# Sheet1.net
KiCad netlist of a schematic drawn in Altium Designer
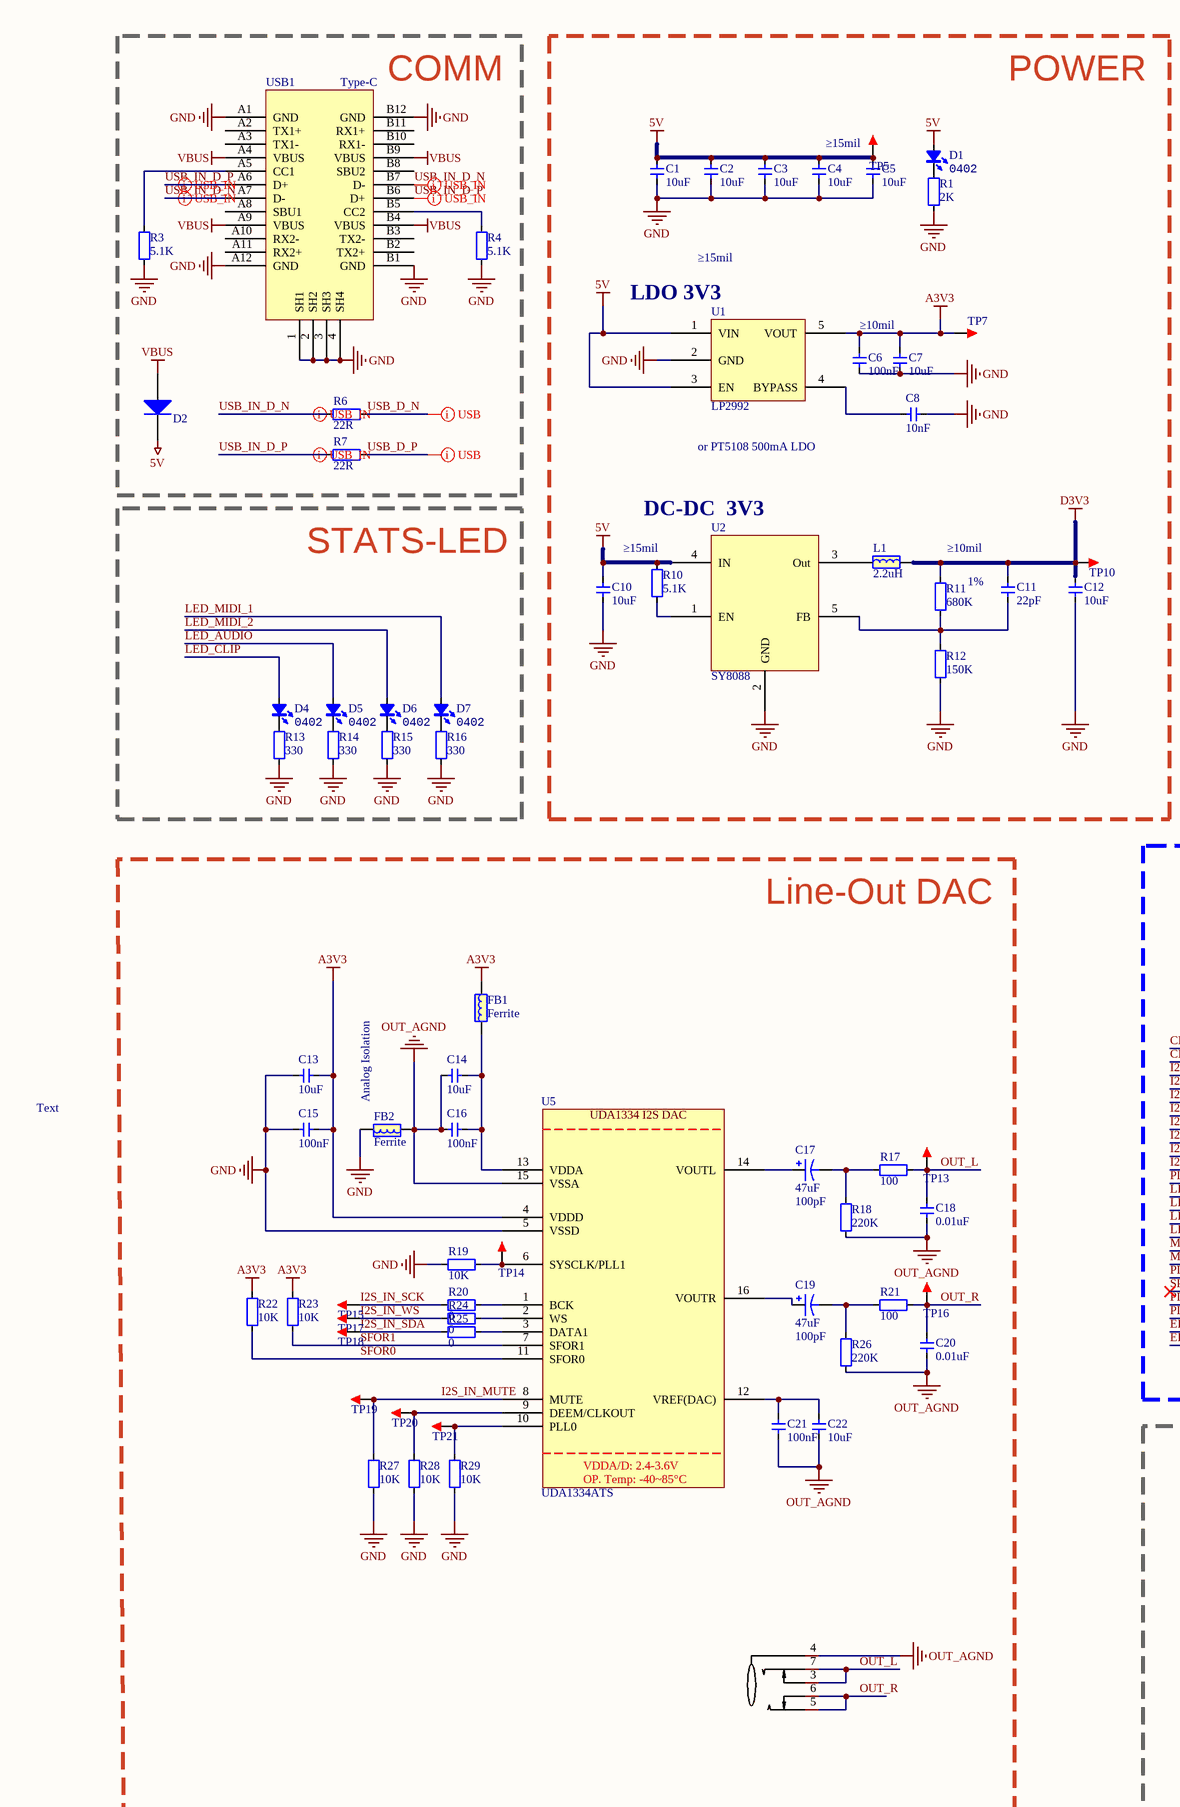
[diagram p0: Sheet1.SchDoc, left]
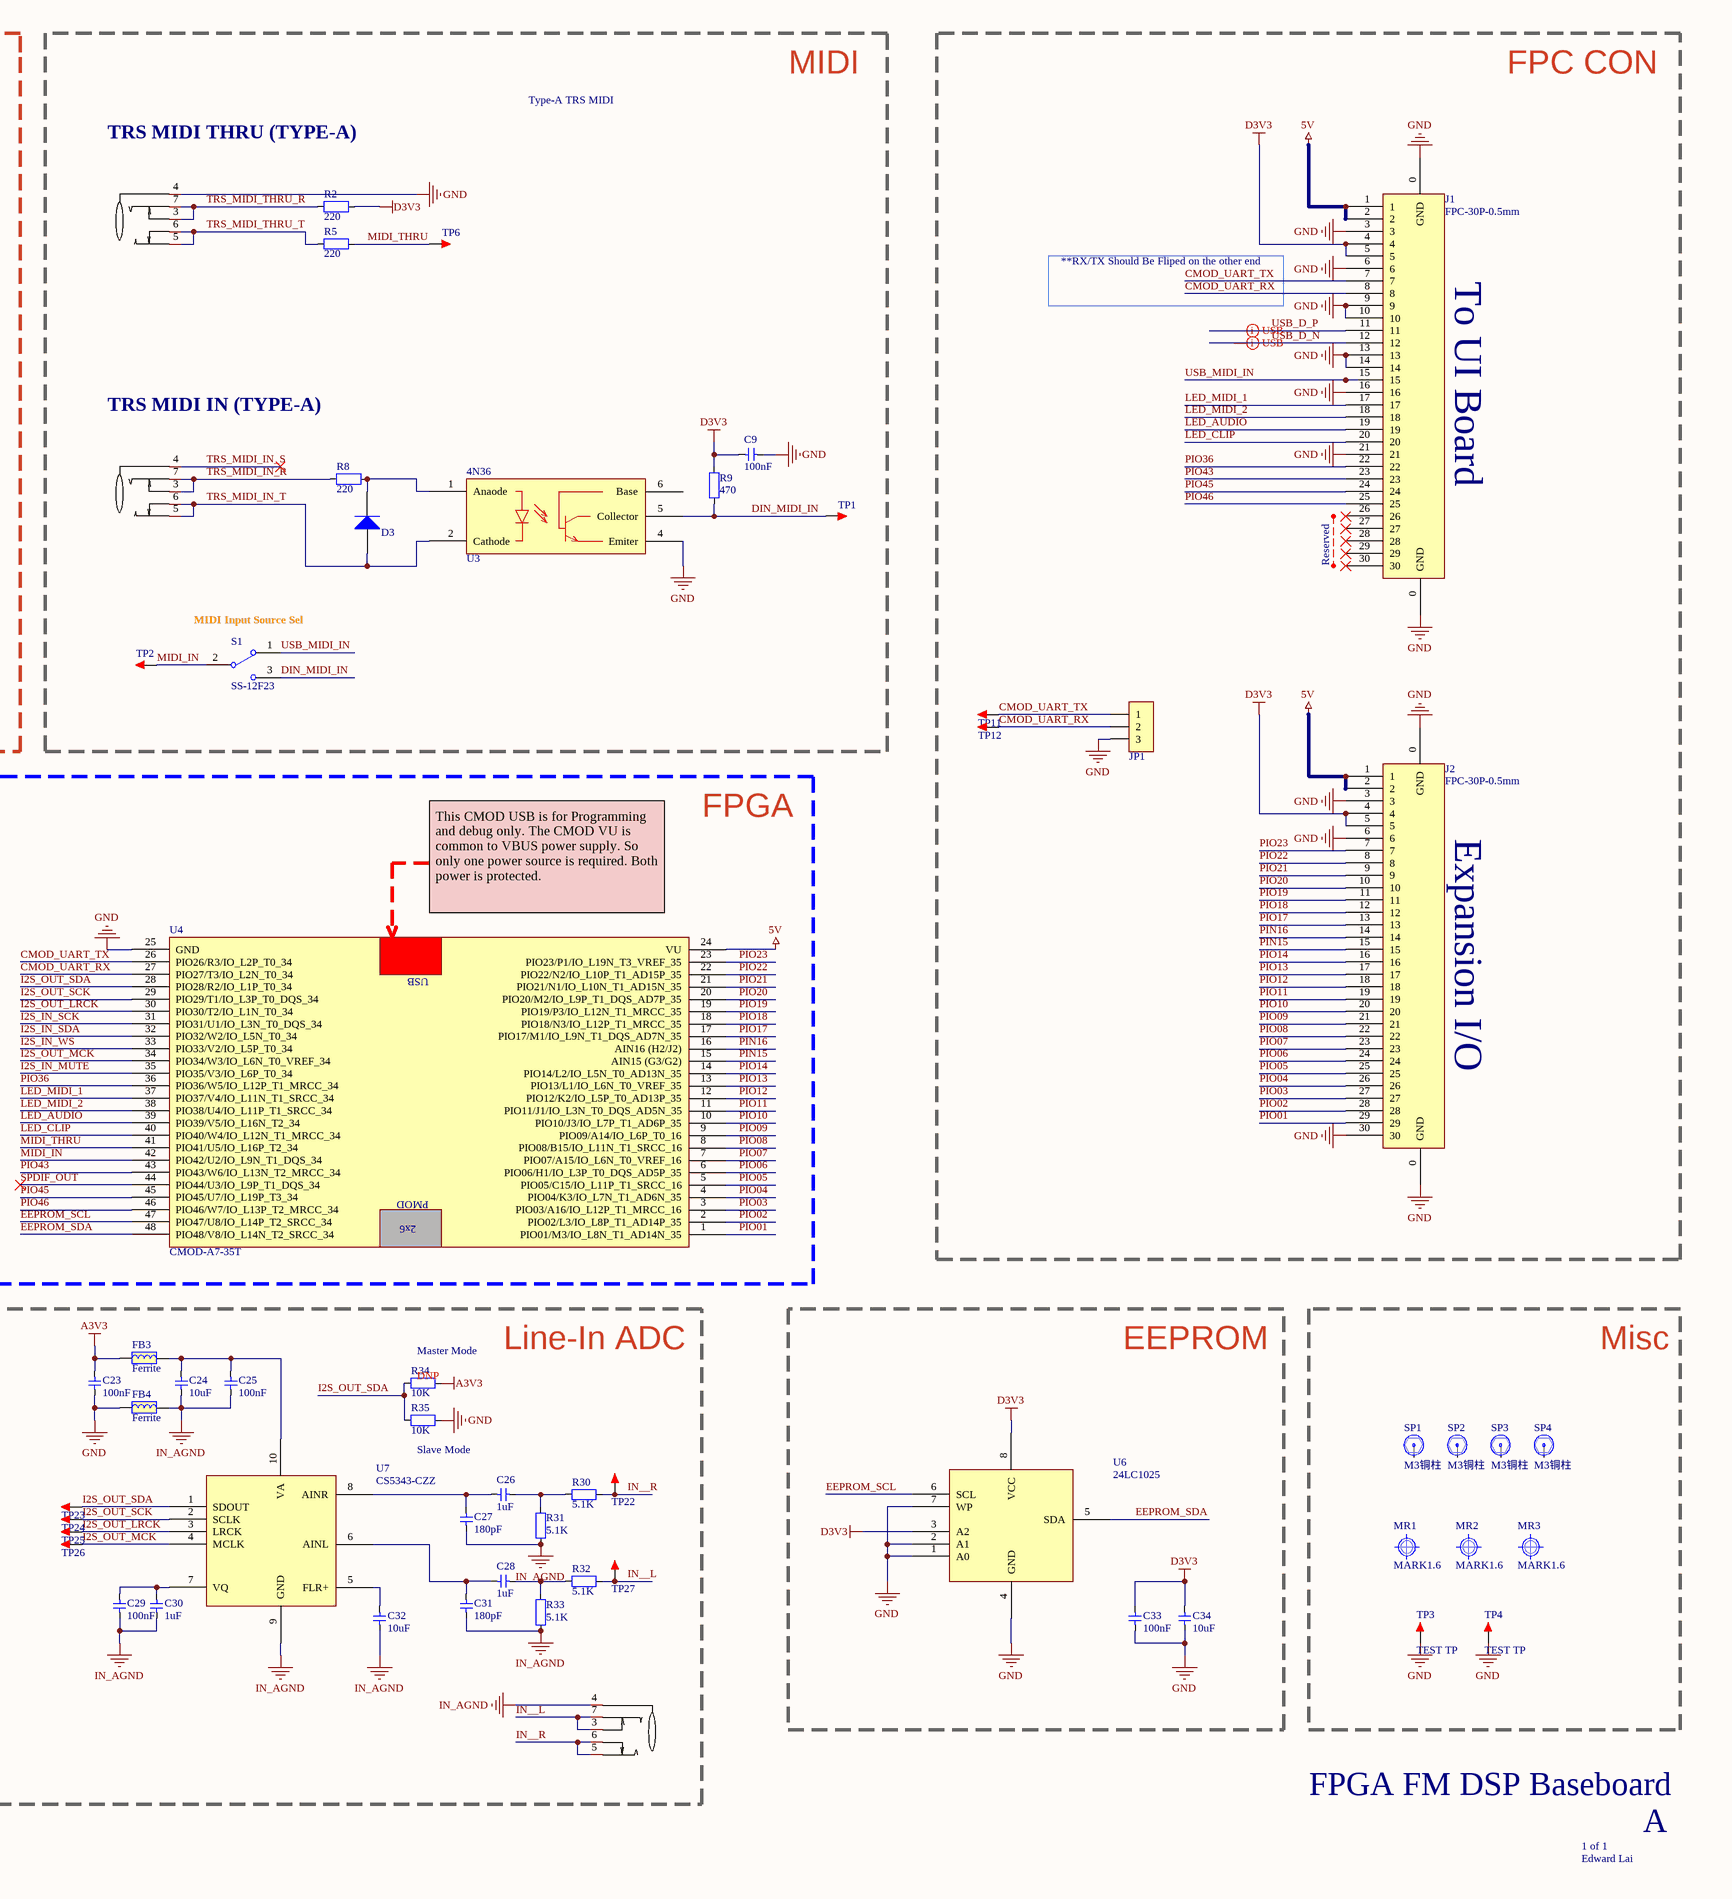
[diagram p1: Sheet1.SchDoc, right]

(export (version "E")
  (design (tool "Eeschema 10.0.6"))
  (components
    (comp (ref "C1")
      (value "10uF")
      (footprint "C0402_L")
      (description "Capacitor")
      (libsource (lib "MyPcbLib") (part "电容-1206"))
    )
    (comp (ref "C2")
      (value "10uF")
      (footprint "C0402_L")
      (description "Capacitor")
      (libsource (lib "MyPcbLib") (part "电容-1206"))
    )
    (comp (ref "C3")
      (value "10uF")
      (footprint "C0402_L")
      (description "Capacitor")
      (libsource (lib "MyPcbLib") (part "电容-1206"))
    )
    (comp (ref "C4")
      (value "10uF")
      (footprint "C0402_L")
      (description "Capacitor")
      (libsource (lib "MyPcbLib") (part "电容-1206"))
    )
    (comp (ref "C5")
      (value "10uF")
      (footprint "C0402_L")
      (description "Capacitor")
      (libsource (lib "MyPcbLib") (part "电容-1206"))
    )
    (comp (ref "C6")
      (value "100nF")
      (footprint "C0402_L")
      (description "Capacitor")
      (libsource (lib "MyPcbLib") (part "电容-0402"))
    )
    (comp (ref "C7")
      (value "10uF")
      (footprint "C0402_L")
      (description "Capacitor")
      (libsource (lib "MyPcbLib") (part "电容-0402"))
    )
    (comp (ref "C8")
      (value "10nF")
      (footprint "C0402_L")
      (description "Capacitor")
      (libsource (lib "MyPcbLib") (part "电容-0402"))
    )
    (comp (ref "C9")
      (value "100nF")
      (footprint "C0402_L")
      (description "Capacitor")
      (libsource (lib "MyPcbLib") (part "电容-0402"))
    )
    (comp (ref "C10")
      (value "10uF")
      (footprint "C0402_L")
      (description "Capacitor")
      (libsource (lib "MyPcbLib") (part "电容-0402"))
    )
    (comp (ref "C11")
      (value "22pF")
      (footprint "C0402_L")
      (description "Capacitor")
      (libsource (lib "MyPcbLib") (part "电容-0402"))
    )
    (comp (ref "C12")
      (value "10uF")
      (footprint "C0402_L")
      (description "Capacitor")
      (libsource (lib "MyPcbLib") (part "电容-0402"))
    )
    (comp (ref "C13")
      (value "10uF")
      (footprint "C0402_L")
      (description "Capacitor")
      (libsource (lib "MyPcbLib") (part "电容-0402"))
    )
    (comp (ref "C14")
      (value "10uF")
      (footprint "C0402_L")
      (description "Capacitor")
      (libsource (lib "MyPcbLib") (part "电容-0402"))
    )
    (comp (ref "C15")
      (value "100nF")
      (footprint "C0402_L")
      (description "Capacitor")
      (libsource (lib "MyPcbLib") (part "电容-0402"))
    )
    (comp (ref "C16")
      (value "100nF")
      (footprint "C0402_L")
      (description "Capacitor")
      (libsource (lib "MyPcbLib") (part "电容-0402"))
    )
    (comp (ref "C17")
      (value "47uF")
      (footprint "CT 5*6 - B")
      (description "Polarized Capacitor SMT")
      (fields (field (name "ALTIUM_VALUE") "100pF") (field (name "PUBLISHER") "Altium Limited"))
      (libsource (lib "Miscellaneous Devices") (part "Cap Pol1"))
    )
    (comp (ref "C18")
      (value "0.01uF")
      (footprint "C0603_L")
      (description "Capacitor")
      (libsource (lib "MyPcbLib") (part "电容-0402"))
    )
    (comp (ref "C19")
      (value "47uF")
      (footprint "CT 5*6 - B")
      (description "Polarized Capacitor SMT")
      (fields (field (name "ALTIUM_VALUE") "100pF") (field (name "PUBLISHER") "Altium Limited"))
      (libsource (lib "Miscellaneous Devices") (part "Cap Pol1"))
    )
    (comp (ref "C20")
      (value "0.01uF")
      (footprint "C0603_L")
      (description "Capacitor")
      (libsource (lib "MyPcbLib") (part "电容-0402"))
    )
    (comp (ref "C21")
      (value "100nF")
      (footprint "C0402_L")
      (description "Capacitor")
      (libsource (lib "MyPcbLib") (part "电容-0402"))
    )
    (comp (ref "C22")
      (value "10uF")
      (footprint "C0402_L")
      (description "Capacitor")
      (libsource (lib "MyPcbLib") (part "电容-0402"))
    )
    (comp (ref "C23")
      (value "100nF")
      (footprint "C0402_L")
      (description "Capacitor")
      (libsource (lib "MyPcbLib") (part "电容-0402"))
    )
    (comp (ref "C24")
      (value "10uF")
      (footprint "C0402_L")
      (description "Capacitor")
      (libsource (lib "MyPcbLib") (part "电容-0402"))
    )
    (comp (ref "C25")
      (value "100nF")
      (footprint "C0402_L")
      (description "Capacitor")
      (libsource (lib "MyPcbLib") (part "电容-0402"))
    )
    (comp (ref "C26")
      (value "1uF")
      (footprint "C0402_L")
      (description "Capacitor")
      (libsource (lib "MyPcbLib") (part "电容-0402"))
    )
    (comp (ref "C27")
      (value "180pF")
      (footprint "C0402_L")
      (description "Capacitor")
      (libsource (lib "MyPcbLib") (part "电容-0402"))
    )
    (comp (ref "C28")
      (value "1uF")
      (footprint "C0402_L")
      (description "Capacitor")
      (libsource (lib "MyPcbLib") (part "电容-0402"))
    )
    (comp (ref "C29")
      (value "100nF")
      (footprint "C0402_L")
      (description "Capacitor")
      (libsource (lib "MyPcbLib") (part "电容-0402"))
    )
    (comp (ref "C30")
      (value "1uF")
      (footprint "C0402_L")
      (description "Capacitor")
      (libsource (lib "MyPcbLib") (part "电容-0402"))
    )
    (comp (ref "C31")
      (value "180pF")
      (footprint "C0402_L")
      (description "Capacitor")
      (libsource (lib "MyPcbLib") (part "电容-0402"))
    )
    (comp (ref "C32")
      (value "10uF")
      (footprint "C0402_L")
      (description "Capacitor")
      (libsource (lib "MyPcbLib") (part "电容-0402"))
    )
    (comp (ref "C33")
      (value "100nF")
      (footprint "C0402_L")
      (description "Capacitor")
      (libsource (lib "MyPcbLib") (part "电容-0402"))
    )
    (comp (ref "C34")
      (value "10uF")
      (footprint "C0402_L")
      (description "Capacitor")
      (libsource (lib "MyPcbLib") (part "电容-0402"))
    )
    (comp (ref "CN1")
      (value "PJ-328-5A")
      (footprint "AUDIO-SMD_PJ-328-5A")
      (fields (field (name "MANUFACTURER") "韩国韩荣"))
      (libsource (lib "altium-import") (part "root_0_PJ-328-5A_"))
    )
    (comp (ref "CN2")
      (value "PJ-328-5A")
      (footprint "AUDIO-SMD_PJ-328-5A")
      (fields (field (name "MANUFACTURER") "韩国韩荣"))
      (libsource (lib "altium-import") (part "root_0_PJ-328-5A_"))
    )
    (comp (ref "CN3")
      (value "PJ-328-5A")
      (footprint "AUDIO-SMD_PJ-328-5A")
      (fields (field (name "MANUFACTURER") "韩国韩荣"))
      (libsource (lib "altium-import") (part "root_0_PJ-328-5A_"))
    )
    (comp (ref "CN4")
      (value "PJ-328-5A")
      (footprint "AUDIO-SMD_PJ-328-5A")
      (fields (field (name "MANUFACTURER") "韩国韩荣"))
      (libsource (lib "altium-import") (part "root_0_mirrored_PJ-328-5A_"))
    )
    (comp (ref "D1")
      (value "color?")
      (footprint "LED0603_R")
      (description "LED")
      (fields (field (name "TYPE") "0402"))
      (libsource (lib "KitSprout") (part "LED_0402"))
    )
    (comp (ref "D2")
      (value "二极管-5B5819WS")
      (footprint "SOD-323")
      (description "40V")
      (libsource (lib "MyPcbLib") (part "二极管-5B5817WS"))
    )
    (comp (ref "D3")
      (value "Diode")
      (footprint "SOD-523")
      (description "1N1418")
      (libsource (lib "0.2 - 二极管-TVS-ESD-整流桥") (part "Diode"))
    )
    (comp (ref "D4")
      (value "color?")
      (footprint "LED0603_R")
      (description "LED")
      (fields (field (name "TYPE") "0402"))
      (libsource (lib "KitSprout") (part "LED_0402"))
    )
    (comp (ref "D5")
      (value "color?")
      (footprint "LED0603_G")
      (description "LED")
      (fields (field (name "TYPE") "0402"))
      (libsource (lib "KitSprout") (part "LED_0402"))
    )
    (comp (ref "D6")
      (value "color?")
      (footprint "LED0603_W")
      (description "LED")
      (fields (field (name "TYPE") "0402"))
      (libsource (lib "KitSprout") (part "LED_0402"))
    )
    (comp (ref "D7")
      (value "color?")
      (footprint "LED0603_W")
      (description "LED")
      (fields (field (name "TYPE") "0402"))
      (libsource (lib "KitSprout") (part "LED_0402"))
    )
    (comp (ref "FB1") (value "Ferrite") (footprint "L0402") (libsource (lib "") (part "电感-201612_2")))
    (comp (ref "FB2") (value "Ferrite") (footprint "L0402") (libsource (lib "MyPcbLib") (part "电感-201612")))
    (comp (ref "FB3") (value "Ferrite") (footprint "L0402") (libsource (lib "") (part "电感-201612_1")))
    (comp (ref "FB4") (value "Ferrite") (footprint "L0402") (libsource (lib "") (part "电感-201612_1")))
    (comp (ref "J1")
      (value "FPC-30P-0.5mm")
      (footprint "FPC0.5-WT-30P")
      (libsource (lib "Schlib2") (part "FPC-30P-0.5mm"))
    )
    (comp (ref "J2")
      (value "FPC-30P-0.5mm")
      (footprint "FPC0.5-WT-30P")
      (libsource (lib "Schlib2") (part "FPC-30P-0.5mm"))
    )
    (comp (ref "JP1")
      (value "HDR-1X3")
      (footprint "XH2.54-LS-3P")
      (description "3P接插件")
      (libsource (lib "5.5 - 2.54mm(100mil)连接器(XH2.54)") (part "Header 3"))
    )
    (comp (ref "L1") (value "2.2uH") (footprint "IND-201612") (libsource (lib "") (part "电感-201612_1")))
    (comp (ref "MR1")
      (value "MARK1.6")
      (footprint "Mark 1.6")
      (description "光学定位点")
      (libsource (lib "0.5 - 按键-开关-蜂鸣器-保险丝-电池-测试点-Mark点") (part "MARK"))
    )
    (comp (ref "MR2")
      (value "MARK1.6")
      (footprint "Mark 1.6")
      (description "光学定位点")
      (libsource (lib "0.5 - 按键-开关-蜂鸣器-保险丝-电池-测试点-Mark点") (part "MARK"))
    )
    (comp (ref "MR3")
      (value "MARK1.6")
      (footprint "Mark 1.6")
      (description "光学定位点")
      (libsource (lib "0.5 - 按键-开关-蜂鸣器-保险丝-电池-测试点-Mark点") (part "MARK"))
    )
    (comp (ref "R1")
      (value "2K")
      (footprint "R0402_L")
      (description "Resistor")
      (libsource (lib "") (part "电阻-0402_2"))
    )
    (comp (ref "R2")
      (value "220")
      (footprint "R0402_L")
      (description "Resistor")
      (libsource (lib "") (part "电阻-0402_3"))
    )
    (comp (ref "R3")
      (value "5.1K")
      (footprint "R0402_L")
      (description "Resistor")
      (libsource (lib "MyPcbLib") (part "电阻-0402"))
    )
    (comp (ref "R4")
      (value "5.1K")
      (footprint "R0402_L")
      (description "Resistor")
      (libsource (lib "MyPcbLib") (part "电阻-0402"))
    )
    (comp (ref "R5")
      (value "220")
      (footprint "R0402_L")
      (description "Resistor")
      (libsource (lib "") (part "电阻-0402_3"))
    )
    (comp (ref "R6")
      (value "22R")
      (footprint "R0402_L")
      (description "Resistor")
      (libsource (lib "") (part "电阻-0402_1"))
    )
    (comp (ref "R7")
      (value "22R")
      (footprint "R0402_L")
      (description "Resistor")
      (libsource (lib "") (part "电阻-0402_1"))
    )
    (comp (ref "R8")
      (value "220")
      (footprint "R0402_L")
      (description "Resistor")
      (libsource (lib "") (part "电阻-0402_3"))
    )
    (comp (ref "R9")
      (value "470")
      (footprint "R0402_L")
      (description "Resistor")
      (libsource (lib "") (part "电阻-0402_2"))
    )
    (comp (ref "R10")
      (value "5.1K")
      (footprint "R0402_L")
      (description "Resistor")
      (libsource (lib "MyPcbLib") (part "电阻-0402"))
    )
    (comp (ref "R11")
      (value "680K")
      (footprint "R0402_L")
      (description "Resistor")
      (fields (field (name "PARAMETER 1") "1%"))
      (libsource (lib "MyPcbLib") (part "电阻-0402"))
    )
    (comp (ref "R12")
      (value "150K")
      (footprint "R0402_L")
      (description "Resistor")
      (libsource (lib "MyPcbLib") (part "电阻-0402"))
    )
    (comp (ref "R13")
      (value "330")
      (footprint "R0402_L")
      (description "Resistor")
      (libsource (lib "") (part "电阻-0402_2"))
    )
    (comp (ref "R14")
      (value "330")
      (footprint "R0402_L")
      (description "Resistor")
      (libsource (lib "") (part "电阻-0402_2"))
    )
    (comp (ref "R15")
      (value "330")
      (footprint "R0402_L")
      (description "Resistor")
      (libsource (lib "") (part "电阻-0402_2"))
    )
    (comp (ref "R16")
      (value "330")
      (footprint "R0402_L")
      (description "Resistor")
      (libsource (lib "") (part "电阻-0402_2"))
    )
    (comp (ref "R17")
      (value "100")
      (footprint "R0603_L")
      (description "Resistor")
      (libsource (lib "") (part "电阻-0402_1"))
    )
    (comp (ref "R18")
      (value "220K")
      (footprint "R0603_L")
      (description "Resistor")
      (libsource (lib "MyPcbLib") (part "电阻-0402"))
    )
    (comp (ref "R19")
      (value "10K")
      (footprint "R0402_L")
      (description "Resistor")
      (libsource (lib "") (part "电阻-0402_1"))
    )
    (comp (ref "R20")
      (value "0")
      (footprint "R0402_L")
      (description "Resistor")
      (libsource (lib "") (part "电阻-0402_3"))
    )
    (comp (ref "R21")
      (value "100")
      (footprint "R0603_L")
      (description "Resistor")
      (libsource (lib "") (part "电阻-0402_1"))
    )
    (comp (ref "R22")
      (value "10K")
      (footprint "R0402_L")
      (description "Resistor")
      (libsource (lib "MyPcbLib") (part "电阻-0402"))
    )
    (comp (ref "R23")
      (value "10K")
      (footprint "R0402_L")
      (description "Resistor")
      (libsource (lib "MyPcbLib") (part "电阻-0402"))
    )
    (comp (ref "R24")
      (value "0")
      (footprint "R0402_L")
      (description "Resistor")
      (libsource (lib "") (part "电阻-0402_3"))
    )
    (comp (ref "R25")
      (value "0")
      (footprint "R0402_L")
      (description "Resistor")
      (libsource (lib "") (part "电阻-0402_3"))
    )
    (comp (ref "R26")
      (value "220K")
      (footprint "R0603_L")
      (description "Resistor")
      (libsource (lib "MyPcbLib") (part "电阻-0402"))
    )
    (comp (ref "R27")
      (value "10K")
      (footprint "R0402_L")
      (description "Resistor")
      (libsource (lib "MyPcbLib") (part "电阻-0402"))
    )
    (comp (ref "R28")
      (value "10K")
      (footprint "R0402_L")
      (description "Resistor")
      (libsource (lib "MyPcbLib") (part "电阻-0402"))
    )
    (comp (ref "R29")
      (value "10K")
      (footprint "R0402_L")
      (description "Resistor")
      (libsource (lib "MyPcbLib") (part "电阻-0402"))
    )
    (comp (ref "R30")
      (value "5.1K")
      (footprint "R0402_L")
      (description "Resistor")
      (libsource (lib "") (part "电阻-0402_1"))
    )
    (comp (ref "R31")
      (value "5.1K")
      (footprint "R0402_L")
      (description "Resistor")
      (libsource (lib "MyPcbLib") (part "电阻-0402"))
    )
    (comp (ref "R32")
      (value "5.1K")
      (footprint "R0402_L")
      (description "Resistor")
      (libsource (lib "") (part "电阻-0402_3"))
    )
    (comp (ref "R33")
      (value "5.1K")
      (footprint "R0402_L")
      (description "Resistor")
      (libsource (lib "MyPcbLib") (part "电阻-0402"))
    )
    (comp (ref "R34")
      (value "10K")
      (footprint "R0402_L")
      (description "Resistor")
      (libsource (lib "") (part "电阻-0402_1"))
    )
    (comp (ref "R35")
      (value "10K")
      (footprint "R0402_L")
      (description "Resistor")
      (libsource (lib "") (part "电阻-0402_1"))
    )
    (comp (ref "S1")
      (value "SS-12F23")
      (footprint "MSK-12C01-07")
      (description "1路波动开关")
      (libsource (lib "0.5 - 按键-开关-蜂鸣器-保险丝-电池-测试点-Mark点") (part "SSW-1P"))
    )
    (comp (ref "SP1")
      (value "M3铜柱")
      (footprint "M3x8_N")
      (description "铜柱")
      (libsource (lib "0.5 - 按键-开关-蜂鸣器-保险丝-电池-测试点-Mark点") (part "铜柱大焊盘"))
    )
    (comp (ref "SP2")
      (value "M3铜柱")
      (footprint "M3x8_N")
      (description "铜柱")
      (libsource (lib "0.5 - 按键-开关-蜂鸣器-保险丝-电池-测试点-Mark点") (part "铜柱大焊盘"))
    )
    (comp (ref "SP3")
      (value "M3铜柱")
      (footprint "M3x8_N")
      (description "铜柱")
      (libsource (lib "0.5 - 按键-开关-蜂鸣器-保险丝-电池-测试点-Mark点") (part "铜柱大焊盘"))
    )
    (comp (ref "SP4")
      (value "M3铜柱")
      (footprint "M3x8_N")
      (description "铜柱")
      (libsource (lib "0.5 - 按键-开关-蜂鸣器-保险丝-电池-测试点-Mark点") (part "铜柱大焊盘"))
    )
    (comp (ref "TP1")
      (value "DIN_MIDI_IN")
      (footprint "TEST 1.2")
      (description "测试环")
      (libsource (lib "0.5 - 按键-开关-蜂鸣器-保险丝-电池-测试点-Mark点") (part "TEST TP"))
    )
    (comp (ref "TP2")
      (value "MIDI_IN")
      (footprint "TEST 1.2")
      (description "测试环")
      (libsource (lib "0.5 - 按键-开关-蜂鸣器-保险丝-电池-测试点-Mark点") (part "TEST TP"))
    )
    (comp (ref "TP3")
      (value "TEST TP")
      (footprint "TEST 1.2")
      (description "测试环")
      (libsource (lib "0.5 - 按键-开关-蜂鸣器-保险丝-电池-测试点-Mark点") (part "TEST TP"))
    )
    (comp (ref "TP4")
      (value "TEST TP")
      (footprint "TEST 1.2")
      (description "测试环")
      (libsource (lib "0.5 - 按键-开关-蜂鸣器-保险丝-电池-测试点-Mark点") (part "TEST TP"))
    )
    (comp (ref "TP5")
      (value "DIN_MIDI_IN")
      (footprint "TEST 1.2")
      (description "测试环")
      (libsource (lib "0.5 - 按键-开关-蜂鸣器-保险丝-电池-测试点-Mark点") (part "TEST TP"))
    )
    (comp (ref "TP6")
      (value "DIN_MIDI_IN")
      (footprint "TEST 1.2")
      (description "测试环")
      (libsource (lib "0.5 - 按键-开关-蜂鸣器-保险丝-电池-测试点-Mark点") (part "TEST TP"))
    )
    (comp (ref "TP7")
      (value "DIN_MIDI_IN")
      (footprint "TEST 1.2")
      (description "测试环")
      (libsource (lib "0.5 - 按键-开关-蜂鸣器-保险丝-电池-测试点-Mark点") (part "TEST TP"))
    )
    (comp (ref "TP10")
      (value "DIN_MIDI_IN")
      (footprint "TEST 1.2")
      (description "测试环")
      (libsource (lib "0.5 - 按键-开关-蜂鸣器-保险丝-电池-测试点-Mark点") (part "TEST TP"))
    )
    (comp (ref "TP11")
      (value "DIN_MIDI_IN")
      (footprint "TEST 1.2")
      (description "测试环")
      (libsource (lib "0.5 - 按键-开关-蜂鸣器-保险丝-电池-测试点-Mark点") (part "TEST TP"))
    )
    (comp (ref "TP12")
      (value "DIN_MIDI_IN")
      (footprint "TEST 1.2")
      (description "测试环")
      (libsource (lib "0.5 - 按键-开关-蜂鸣器-保险丝-电池-测试点-Mark点") (part "TEST TP"))
    )
    (comp (ref "TP13")
      (value "DIN_MIDI_IN")
      (footprint "TEST 1.2")
      (description "测试环")
      (libsource (lib "0.5 - 按键-开关-蜂鸣器-保险丝-电池-测试点-Mark点") (part "TEST TP"))
    )
    (comp (ref "TP14")
      (value "DIN_MIDI_IN")
      (footprint "TEST 1.2")
      (description "测试环")
      (libsource (lib "0.5 - 按键-开关-蜂鸣器-保险丝-电池-测试点-Mark点") (part "TEST TP"))
    )
    (comp (ref "TP15")
      (value "DIN_MIDI_IN")
      (footprint "TEST 1.2")
      (description "测试环")
      (libsource (lib "0.5 - 按键-开关-蜂鸣器-保险丝-电池-测试点-Mark点") (part "TEST TP"))
    )
    (comp (ref "TP16")
      (value "DIN_MIDI_IN")
      (footprint "TEST 1.2")
      (description "测试环")
      (libsource (lib "0.5 - 按键-开关-蜂鸣器-保险丝-电池-测试点-Mark点") (part "TEST TP"))
    )
    (comp (ref "TP17")
      (value "DIN_MIDI_IN")
      (footprint "TEST 1.2")
      (description "测试环")
      (libsource (lib "0.5 - 按键-开关-蜂鸣器-保险丝-电池-测试点-Mark点") (part "TEST TP"))
    )
    (comp (ref "TP18")
      (value "DIN_MIDI_IN")
      (footprint "TEST 1.2")
      (description "测试环")
      (libsource (lib "0.5 - 按键-开关-蜂鸣器-保险丝-电池-测试点-Mark点") (part "TEST TP"))
    )
    (comp (ref "TP19")
      (value "DIN_MIDI_IN")
      (footprint "TEST 1.2")
      (description "测试环")
      (libsource (lib "0.5 - 按键-开关-蜂鸣器-保险丝-电池-测试点-Mark点") (part "TEST TP"))
    )
    (comp (ref "TP20")
      (value "DIN_MIDI_IN")
      (footprint "TEST 1.2")
      (description "测试环")
      (libsource (lib "0.5 - 按键-开关-蜂鸣器-保险丝-电池-测试点-Mark点") (part "TEST TP"))
    )
    (comp (ref "TP21")
      (value "DIN_MIDI_IN")
      (footprint "TEST 1.2")
      (description "测试环")
      (libsource (lib "0.5 - 按键-开关-蜂鸣器-保险丝-电池-测试点-Mark点") (part "TEST TP"))
    )
    (comp (ref "TP22")
      (value "DIN_MIDI_IN")
      (footprint "TEST 1.2")
      (description "测试环")
      (libsource (lib "0.5 - 按键-开关-蜂鸣器-保险丝-电池-测试点-Mark点") (part "TEST TP"))
    )
    (comp (ref "TP23")
      (value "DIN_MIDI_IN")
      (footprint "TEST 1.2")
      (description "测试环")
      (libsource (lib "0.5 - 按键-开关-蜂鸣器-保险丝-电池-测试点-Mark点") (part "TEST TP"))
    )
    (comp (ref "TP24")
      (value "DIN_MIDI_IN")
      (footprint "TEST 1.2")
      (description "测试环")
      (libsource (lib "0.5 - 按键-开关-蜂鸣器-保险丝-电池-测试点-Mark点") (part "TEST TP"))
    )
    (comp (ref "TP25")
      (value "DIN_MIDI_IN")
      (footprint "TEST 1.2")
      (description "测试环")
      (libsource (lib "0.5 - 按键-开关-蜂鸣器-保险丝-电池-测试点-Mark点") (part "TEST TP"))
    )
    (comp (ref "TP26")
      (value "DIN_MIDI_IN")
      (footprint "TEST 1.2")
      (description "测试环")
      (libsource (lib "0.5 - 按键-开关-蜂鸣器-保险丝-电池-测试点-Mark点") (part "TEST TP"))
    )
    (comp (ref "TP27")
      (value "DIN_MIDI_IN")
      (footprint "TEST 1.2")
      (description "测试环")
      (libsource (lib "0.5 - 按键-开关-蜂鸣器-保险丝-电池-测试点-Mark点") (part "TEST TP"))
    )
    (comp (ref "U1") (value "LP2992") (footprint "SOT23-5M") (libsource (lib "Schlib2") (part "LP2992")))
    (comp (ref "U2")
      (value "SY8088")
      (footprint "SOT23-5")
      (description "SY8088 High Efficiency 1.5MHz, 1A  \r\nSynchronous Step Down Regulator")
      (libsource (lib "Schlib2") (part "SY8088"))
    )
    (comp (ref "U3")
      (value "4N36")
      (footprint "OPTOCOUPLER_H11F3SR2M")
      (description "4N36\r\n6-Pin General Purpose Phototransistor Optocouplers")
      (libsource (lib "Schlib2") (part "4N36"))
    )
    (comp (ref "U4")
      (value "CMOD-A7-35T")
      (footprint "DIP48")
      (description "Digilent CMOD A7 35T")
      (libsource (lib "Schlib2") (part "CMOD-A7-35T"))
    )
    (comp (ref "U5")
      (value "UDA1334ATS")
      (footprint "SSOP16")
      (libsource (lib "Schlib2") (part "UDA1334ATS"))
    )
    (comp (ref "U6")
      (value "24LC1025")
      (footprint "SOIC-8")
      (description "24LC1025 EEPROM")
      (libsource (lib "Schlib2") (part "24LC1025"))
    )
    (comp (ref "U7")
      (value "CS5343-CZZ")
      (footprint "MSOP10_M")
      (description "98dB 96kHz Multi-Bit Audio ADC")
      (libsource (lib "Schlib2") (part "CS5343-CZZ"))
    )
    (comp (ref "USB1")
      (value "Type-C")
      (footprint "Type-C-TOP")
      (libsource (lib "MyPcbLib") (part "USB-Type-C-TOP"))
    )
  )
  (nets
    (net (code "1") (name "/CMOD_UART_RX") (class "Default")
      (node (ref "J1") (pin "8") (pinfunction "8_8") (pintype "passive"))
      (node (ref "JP1") (pin "2") (pinfunction "2_2") (pintype "passive"))
      (node (ref "TP12") (pin "1") (pinfunction "1_1") (pintype "passive"))
      (node (ref "U4") (pin "27") (pinfunction "PIO27/T3/IO_L2N_T0_34_27") (pintype "passive"))
    )
    (net (code "2") (name "/CMOD_UART_TX") (class "Default")
      (node (ref "J1") (pin "7") (pinfunction "7_7") (pintype "passive"))
      (node (ref "JP1") (pin "1") (pinfunction "1_1") (pintype "passive"))
      (node (ref "TP11") (pin "1") (pinfunction "1_1") (pintype "passive"))
      (node (ref "U4") (pin "26") (pinfunction "PIO26/R3/IO_L2P_T0_34_26") (pintype "passive"))
    )
    (net (code "3") (name "/DIN_MIDI_IN") (class "Default")
      (node (ref "R9") (pin "1") (pinfunction "1_1") (pintype "passive"))
      (node (ref "S1") (pin "3") (pinfunction "3_3") (pintype "passive"))
      (node (ref "TP1") (pin "1") (pinfunction "1_1") (pintype "passive"))
      (node (ref "U3") (pin "5") (pinfunction "Collector_5") (pintype "passive"))
    )
    (net (code "4") (name "/EEPROM_SCL") (class "Default")
      (node (ref "U4") (pin "47") (pinfunction "PIO47/U8/IO_L14P_T2_SRCC_34_47") (pintype "passive"))
      (node (ref "U6") (pin "6") (pinfunction "SCL_6") (pintype "passive"))
    )
    (net (code "5") (name "/EEPROM_SDA") (class "Default")
      (node (ref "U4") (pin "48") (pinfunction "PIO48/V8/IO_L14N_T2_SRCC_34_48") (pintype "passive"))
      (node (ref "U6") (pin "5") (pinfunction "SDA_5") (pintype "passive"))
    )
    (net (code "6") (name "/I2S_IN_MUTE") (class "Default")
      (node (ref "R27") (pin "1") (pinfunction "1_1") (pintype "passive"))
      (node (ref "TP19") (pin "1") (pinfunction "1_1") (pintype "passive"))
      (node (ref "U4") (pin "35") (pinfunction "PIO35/V3/IO_L6P_T0_34_35") (pintype "passive"))
      (node (ref "U5") (pin "8") (pinfunction "MUTE_8") (pintype "passive"))
    )
    (net (code "7") (name "/I2S_IN_SCK") (class "Default")
      (node (ref "R20") (pin "1") (pinfunction "1_1") (pintype "passive"))
      (node (ref "TP15") (pin "1") (pinfunction "1_1") (pintype "passive"))
      (node (ref "U4") (pin "31") (pinfunction "PIO31/U1/IO_L3N_T0_DQS_34_31") (pintype "passive"))
    )
    (net (code "8") (name "/I2S_IN_SDA") (class "Default")
      (node (ref "R25") (pin "1") (pinfunction "1_1") (pintype "passive"))
      (node (ref "TP18") (pin "1") (pinfunction "1_1") (pintype "passive"))
      (node (ref "U4") (pin "32") (pinfunction "PIO32/W2/IO_L5N_T0_34_32") (pintype "passive"))
    )
    (net (code "9") (name "/I2S_IN_WS") (class "Default")
      (node (ref "R24") (pin "1") (pinfunction "1_1") (pintype "passive"))
      (node (ref "TP17") (pin "1") (pinfunction "1_1") (pintype "passive"))
      (node (ref "U4") (pin "33") (pinfunction "PIO33/V2/IO_L5P_T0_34_33") (pintype "passive"))
    )
    (net (code "10") (name "/I2S_OUT_LRCK") (class "Default")
      (node (ref "TP25") (pin "1") (pinfunction "1_1") (pintype "passive"))
      (node (ref "U4") (pin "30") (pinfunction "PIO30/T2/IO_L1N_T0_34_30") (pintype "passive"))
      (node (ref "U7") (pin "3") (pinfunction "LRCK_3") (pintype "passive"))
    )
    (net (code "11") (name "/I2S_OUT_MCK") (class "Default")
      (node (ref "TP26") (pin "1") (pinfunction "1_1") (pintype "passive"))
      (node (ref "U4") (pin "34") (pinfunction "PIO34/W3/IO_L6N_T0_VREF_34_34") (pintype "passive"))
      (node (ref "U7") (pin "4") (pinfunction "MCLK_4") (pintype "passive"))
    )
    (net (code "12") (name "/I2S_OUT_SCK") (class "Default")
      (node (ref "TP24") (pin "1") (pinfunction "1_1") (pintype "passive"))
      (node (ref "U4") (pin "29") (pinfunction "PIO29/T1/IO_L3P_T0_DQS_34_29") (pintype "passive"))
      (node (ref "U7") (pin "2") (pinfunction "SCLK_2") (pintype "passive"))
    )
    (net (code "13") (name "/I2S_OUT_SDA") (class "Default")
      (node (ref "R34") (pin "2") (pinfunction "2_2") (pintype "passive"))
      (node (ref "R35") (pin "2") (pinfunction "2_2") (pintype "passive"))
      (node (ref "TP23") (pin "1") (pinfunction "1_1") (pintype "passive"))
      (node (ref "U4") (pin "28") (pinfunction "PIO28/R2/IO_L1P_T0_34_28") (pintype "passive"))
      (node (ref "U7") (pin "1") (pinfunction "SDOUT_1") (pintype "passive"))
    )
    (net (code "14") (name "/IN__L") (class "Default")
      (node (ref "CN4") (pin "3") (pinfunction "3_3") (pintype "passive"))
      (node (ref "CN4") (pin "7") (pinfunction "7_7") (pintype "passive"))
      (node (ref "R32") (pin "2") (pinfunction "2_2") (pintype "passive"))
      (node (ref "TP27") (pin "1") (pinfunction "1_1") (pintype "passive"))
    )
    (net (code "15") (name "/IN__R") (class "Default")
      (node (ref "CN4") (pin "5") (pinfunction "5_5") (pintype "passive"))
      (node (ref "CN4") (pin "6") (pinfunction "6_6") (pintype "passive"))
      (node (ref "R30") (pin "1") (pinfunction "1_1") (pintype "passive"))
      (node (ref "TP22") (pin "1") (pinfunction "1_1") (pintype "passive"))
    )
    (net (code "16") (name "/LED_AUDIO") (class "Default")
      (node (ref "D5") (pin "1") (pinfunction "A_1") (pintype "passive"))
      (node (ref "J1") (pin "19") (pinfunction "19_19") (pintype "passive"))
      (node (ref "U4") (pin "39") (pinfunction "PIO39/V5/IO_L16N_T2_34_39") (pintype "passive"))
    )
    (net (code "17") (name "/LED_CLIP") (class "Default")
      (node (ref "D4") (pin "1") (pinfunction "A_1") (pintype "passive"))
      (node (ref "J1") (pin "20") (pinfunction "20_20") (pintype "passive"))
      (node (ref "U4") (pin "40") (pinfunction "PIO40/W4/IO_L12N_T1_MRCC_34_40") (pintype "passive"))
    )
    (net (code "18") (name "/LED_MIDI_1") (class "Default")
      (node (ref "D7") (pin "1") (pinfunction "A_1") (pintype "passive"))
      (node (ref "J1") (pin "17") (pinfunction "17_17") (pintype "passive"))
      (node (ref "U4") (pin "37") (pinfunction "PIO37/V4/IO_L11N_T1_SRCC_34_37") (pintype "passive"))
    )
    (net (code "19") (name "/LED_MIDI_2") (class "Default")
      (node (ref "D6") (pin "1") (pinfunction "A_1") (pintype "passive"))
      (node (ref "J1") (pin "18") (pinfunction "18_18") (pintype "passive"))
      (node (ref "U4") (pin "38") (pinfunction "PIO38/U4/IO_L11P_T1_SRCC_34_38") (pintype "passive"))
    )
    (net (code "20") (name "/MIDI_IN") (class "Default")
      (node (ref "S1") (pin "2") (pinfunction "2_2") (pintype "passive"))
      (node (ref "TP2") (pin "1") (pinfunction "1_1") (pintype "passive"))
      (node (ref "U4") (pin "42") (pinfunction "PIO42/U2/IO_L9N_T1_DQS_34_42") (pintype "passive"))
    )
    (net (code "21") (name "/MIDI_THRU") (class "Default")
      (node (ref "R5") (pin "2") (pinfunction "2_2") (pintype "passive"))
      (node (ref "TP6") (pin "1") (pinfunction "1_1") (pintype "passive"))
      (node (ref "U4") (pin "41") (pinfunction "PIO41/U5/IO_L16P_T2_34_41") (pintype "passive"))
    )
    (net (code "22") (name "/OUT_L") (class "Default")
      (node (ref "C18") (pin "2") (pinfunction "2_2") (pintype "passive"))
      (node (ref "CN3") (pin "3") (pinfunction "3_3") (pintype "passive"))
      (node (ref "CN3") (pin "7") (pinfunction "7_7") (pintype "passive"))
      (node (ref "R17") (pin "1") (pinfunction "1_1") (pintype "passive"))
      (node (ref "TP13") (pin "1") (pinfunction "1_1") (pintype "passive"))
    )
    (net (code "23") (name "/OUT_R") (class "Default")
      (node (ref "C20") (pin "2") (pinfunction "2_2") (pintype "passive"))
      (node (ref "CN3") (pin "5") (pinfunction "5_5") (pintype "passive"))
      (node (ref "CN3") (pin "6") (pinfunction "6_6") (pintype "passive"))
      (node (ref "R21") (pin "1") (pinfunction "1_1") (pintype "passive"))
      (node (ref "TP16") (pin "1") (pinfunction "1_1") (pintype "passive"))
    )
    (net (code "24") (name "/PIN15") (class "Default")
      (node (ref "J2") (pin "15") (pinfunction "15_15") (pintype "passive"))
      (node (ref "U4") (pin "15") (pinfunction "AIN15_(G3/G2)_15") (pintype "passive"))
    )
    (net (code "25") (name "/PIN16") (class "Default")
      (node (ref "J2") (pin "14") (pinfunction "14_14") (pintype "passive"))
      (node (ref "U4") (pin "16") (pinfunction "AIN16_(H2/J2)_16") (pintype "passive"))
    )
    (net (code "26") (name "/PIO01") (class "Default")
      (node (ref "J2") (pin "29") (pinfunction "29_29") (pintype "passive"))
      (node (ref "U4") (pin "1") (pinfunction "PIO01/M3/IO_L8N_T1_AD14N_35_1") (pintype "passive"))
    )
    (net (code "27") (name "/PIO02") (class "Default")
      (node (ref "J2") (pin "28") (pinfunction "28_28") (pintype "passive"))
      (node (ref "U4") (pin "2") (pinfunction "PIO02/L3/IO_L8P_T1_AD14P_35_2") (pintype "passive"))
    )
    (net (code "28") (name "/PIO03") (class "Default")
      (node (ref "J2") (pin "27") (pinfunction "27_27") (pintype "passive"))
      (node (ref "U4") (pin "3") (pinfunction "PIO03/A16/IO_L12P_T1_MRCC_16_3") (pintype "passive"))
    )
    (net (code "29") (name "/PIO04") (class "Default")
      (node (ref "J2") (pin "26") (pinfunction "26_26") (pintype "passive"))
      (node (ref "U4") (pin "4") (pinfunction "PIO04/K3/IO_L7N_T1_AD6N_35_4") (pintype "passive"))
    )
    (net (code "30") (name "/PIO05") (class "Default")
      (node (ref "J2") (pin "25") (pinfunction "25_25") (pintype "passive"))
      (node (ref "U4") (pin "5") (pinfunction "PIO05/C15/IO_L11P_T1_SRCC_16_5") (pintype "passive"))
    )
    (net (code "31") (name "/PIO06") (class "Default")
      (node (ref "J2") (pin "24") (pinfunction "24_24") (pintype "passive"))
      (node (ref "U4") (pin "6") (pinfunction "PIO06/H1/IO_L3P_T0_DQS_AD5P_35_6") (pintype "passive"))
    )
    (net (code "32") (name "/PIO07") (class "Default")
      (node (ref "J2") (pin "23") (pinfunction "23_23") (pintype "passive"))
      (node (ref "U4") (pin "7") (pinfunction "PIO07/A15/IO_L6N_T0_VREF_16_7") (pintype "passive"))
    )
    (net (code "33") (name "/PIO08") (class "Default")
      (node (ref "J2") (pin "22") (pinfunction "22_22") (pintype "passive"))
      (node (ref "U4") (pin "8") (pinfunction "PIO08/B15/IO_L11N_T1_SRCC_16_8") (pintype "passive"))
    )
    (net (code "34") (name "/PIO09") (class "Default")
      (node (ref "J2") (pin "21") (pinfunction "21_21") (pintype "passive"))
      (node (ref "U4") (pin "9") (pinfunction "PIO09/A14/IO_L6P_T0_16_9") (pintype "passive"))
    )
    (net (code "35") (name "/PIO10") (class "Default")
      (node (ref "J2") (pin "20") (pinfunction "20_20") (pintype "passive"))
      (node (ref "U4") (pin "10") (pinfunction "PIO10/J3/IO_L7P_T1_AD6P_35_10") (pintype "passive"))
    )
    (net (code "36") (name "/PIO11") (class "Default")
      (node (ref "J2") (pin "19") (pinfunction "19_19") (pintype "passive"))
      (node (ref "U4") (pin "11") (pinfunction "PIO11/J1/IO_L3N_T0_DQS_AD5N_35_11") (pintype "passive"))
    )
    (net (code "37") (name "/PIO12") (class "Default")
      (node (ref "J2") (pin "18") (pinfunction "18_18") (pintype "passive"))
      (node (ref "U4") (pin "12") (pinfunction "PIO12/K2/IO_L5P_T0_AD13P_35_12") (pintype "passive"))
    )
    (net (code "38") (name "/PIO13") (class "Default")
      (node (ref "J2") (pin "17") (pinfunction "17_17") (pintype "passive"))
      (node (ref "U4") (pin "13") (pinfunction "PIO13/L1/IO_L6N_T0_VREF_35_13") (pintype "passive"))
    )
    (net (code "39") (name "/PIO14") (class "Default")
      (node (ref "J2") (pin "16") (pinfunction "16_16") (pintype "passive"))
      (node (ref "U4") (pin "14") (pinfunction "PIO14/L2/IO_L5N_T0_AD13N_35_14") (pintype "passive"))
    )
    (net (code "40") (name "/PIO17") (class "Default")
      (node (ref "J2") (pin "13") (pinfunction "13_13") (pintype "passive"))
      (node (ref "U4") (pin "17") (pinfunction "PIO17/M1/IO_L9N_T1_DQS_AD7N_35_17") (pintype "passive"))
    )
    (net (code "41") (name "/PIO18") (class "Default")
      (node (ref "J2") (pin "12") (pinfunction "12_12") (pintype "passive"))
      (node (ref "U4") (pin "18") (pinfunction "PIO18/N3/IO_L12P_T1_MRCC_35_18") (pintype "passive"))
    )
    (net (code "42") (name "/PIO19") (class "Default")
      (node (ref "J2") (pin "11") (pinfunction "11_11") (pintype "passive"))
      (node (ref "U4") (pin "19") (pinfunction "PIO19/P3/IO_L12N_T1_MRCC_35_19") (pintype "passive"))
    )
    (net (code "43") (name "/PIO20") (class "Default")
      (node (ref "J2") (pin "10") (pinfunction "10_10") (pintype "passive"))
      (node (ref "U4") (pin "20") (pinfunction "PIO20/M2/IO_L9P_T1_DQS_AD7P_35_20") (pintype "passive"))
    )
    (net (code "44") (name "/PIO21") (class "Default")
      (node (ref "J2") (pin "9") (pinfunction "9_9") (pintype "passive"))
      (node (ref "U4") (pin "21") (pinfunction "PIO21/N1/IO_L10N_T1_AD15N_35_21") (pintype "passive"))
    )
    (net (code "45") (name "/PIO22") (class "Default")
      (node (ref "J2") (pin "8") (pinfunction "8_8") (pintype "passive"))
      (node (ref "U4") (pin "22") (pinfunction "PIO22/N2/IO_L10P_T1_AD15P_35_22") (pintype "passive"))
    )
    (net (code "46") (name "/PIO23") (class "Default")
      (node (ref "J2") (pin "7") (pinfunction "7_7") (pintype "passive"))
      (node (ref "U4") (pin "23") (pinfunction "PIO23/P1/IO_L19N_T3_VREF_35_23") (pintype "passive"))
    )
    (net (code "47") (name "/PIO36") (class "Default")
      (node (ref "J1") (pin "22") (pinfunction "22_22") (pintype "passive"))
      (node (ref "U4") (pin "36") (pinfunction "PIO36/W5/IO_L12P_T1_MRCC_34_36") (pintype "passive"))
    )
    (net (code "48") (name "/PIO43") (class "Default")
      (node (ref "J1") (pin "23") (pinfunction "23_23") (pintype "passive"))
      (node (ref "U4") (pin "43") (pinfunction "PIO43/W6/IO_L13N_T2_MRCC_34_43") (pintype "passive"))
    )
    (net (code "49") (name "/PIO45") (class "Default")
      (node (ref "J1") (pin "24") (pinfunction "24_24") (pintype "passive"))
      (node (ref "U4") (pin "45") (pinfunction "PIO45/U7/IO_L19P_T3_34_45") (pintype "passive"))
    )
    (net (code "50") (name "/PIO46") (class "Default")
      (node (ref "J1") (pin "25") (pinfunction "25_25") (pintype "passive"))
      (node (ref "U4") (pin "46") (pinfunction "PIO46/W7/IO_L13P_T2_MRCC_34_46") (pintype "passive"))
    )
    (net (code "51") (name "/SFOR0") (class "Default")
      (node (ref "R22") (pin "2") (pinfunction "2_2") (pintype "passive"))
      (node (ref "U5") (pin "11") (pinfunction "SFOR0_11") (pintype "passive"))
    )
    (net (code "52") (name "/SFOR1") (class "Default")
      (node (ref "R23") (pin "2") (pinfunction "2_2") (pintype "passive"))
      (node (ref "U5") (pin "7") (pinfunction "SFOR1_7") (pintype "passive"))
    )
    (net (code "53") (name "/SPDIF_OUT") (class "Default")
      (node (ref "U4") (pin "44") (pinfunction "PIO44/U3/IO_L9P_T1_DQS_34_44") (pintype "passive+no_connect"))
    )
    (net (code "54") (name "/TRS_MIDI_IN_R") (class "Default")
      (node (ref "CN2") (pin "3") (pinfunction "3_3") (pintype "passive"))
      (node (ref "CN2") (pin "7") (pinfunction "7_7") (pintype "passive"))
      (node (ref "R8") (pin "1") (pinfunction "1_1") (pintype "passive"))
    )
    (net (code "55") (name "/TRS_MIDI_IN_S") (class "Default")
      (node (ref "CN2") (pin "4") (pinfunction "4_4") (pintype "passive+no_connect"))
    )
    (net (code "56") (name "/TRS_MIDI_IN_T") (class "Default")
      (node (ref "CN2") (pin "5") (pinfunction "5_5") (pintype "passive"))
      (node (ref "CN2") (pin "6") (pinfunction "6_6") (pintype "passive"))
      (node (ref "D3") (pin "1") (pinfunction "A_1") (pintype "passive"))
      (node (ref "U3") (pin "2") (pinfunction "Cathode_2") (pintype "passive"))
    )
    (net (code "57") (name "/TRS_MIDI_THRU_R") (class "Default")
      (node (ref "CN1") (pin "3") (pinfunction "3_3") (pintype "passive"))
      (node (ref "CN1") (pin "7") (pinfunction "7_7") (pintype "passive"))
      (node (ref "R2") (pin "1") (pinfunction "1_1") (pintype "passive"))
    )
    (net (code "58") (name "/TRS_MIDI_THRU_T") (class "Default")
      (node (ref "CN1") (pin "5") (pinfunction "5_5") (pintype "passive"))
      (node (ref "CN1") (pin "6") (pinfunction "6_6") (pintype "passive"))
      (node (ref "R5") (pin "1") (pinfunction "1_1") (pintype "passive"))
    )
    (net (code "59") (name "/USB_D_N") (class "Default")
      (node (ref "J1") (pin "12") (pinfunction "12_12") (pintype "passive"))
      (node (ref "R6") (pin "1") (pinfunction "1_1") (pintype "passive"))
    )
    (net (code "60") (name "/USB_D_P") (class "Default")
      (node (ref "J1") (pin "11") (pinfunction "11_11") (pintype "passive"))
      (node (ref "R7") (pin "1") (pinfunction "1_1") (pintype "passive"))
    )
    (net (code "61") (name "/USB_IN_D_N") (class "Default")
      (node (ref "R6") (pin "2") (pinfunction "2_2") (pintype "passive"))
      (node (ref "USB1") (pin "A7") (pinfunction "D-_A7") (pintype "passive"))
      (node (ref "USB1") (pin "B7") (pinfunction "D-_B7") (pintype "passive"))
    )
    (net (code "62") (name "/USB_IN_D_P") (class "Default")
      (node (ref "R7") (pin "2") (pinfunction "2_2") (pintype "passive"))
      (node (ref "USB1") (pin "A6") (pinfunction "D+_A6") (pintype "passive"))
      (node (ref "USB1") (pin "B6") (pinfunction "D+_B6") (pintype "passive"))
    )
    (net (code "63") (name "/USB_MIDI_IN") (class "Default")
      (node (ref "J1") (pin "15") (pinfunction "15_15") (pintype "passive"))
      (node (ref "S1") (pin "1") (pinfunction "1_1") (pintype "passive"))
    )
    (net (code "64") (name "5V") (class "Default")
      (node (ref "C1") (pin "2") (pinfunction "2_2") (pintype "passive"))
      (node (ref "C10") (pin "2") (pinfunction "2_2") (pintype "passive"))
      (node (ref "C2") (pin "2") (pinfunction "2_2") (pintype "passive"))
      (node (ref "C3") (pin "2") (pinfunction "2_2") (pintype "passive"))
      (node (ref "C4") (pin "2") (pinfunction "2_2") (pintype "passive"))
      (node (ref "C5") (pin "2") (pinfunction "2_2") (pintype "passive"))
      (node (ref "D1") (pin "1") (pinfunction "A_1") (pintype "passive"))
      (node (ref "D2") (pin "2") (pinfunction "K_2") (pintype "passive"))
      (node (ref "J1") (pin "1") (pinfunction "1_1") (pintype "passive"))
      (node (ref "J1") (pin "2") (pinfunction "2_2") (pintype "passive"))
      (node (ref "J2") (pin "1") (pinfunction "1_1") (pintype "passive"))
      (node (ref "J2") (pin "2") (pinfunction "2_2") (pintype "passive"))
      (node (ref "R10") (pin "1") (pinfunction "1_1") (pintype "passive"))
      (node (ref "TP5") (pin "1") (pinfunction "1_1") (pintype "passive"))
      (node (ref "U1") (pin "1") (pinfunction "VIN_1") (pintype "passive"))
      (node (ref "U1") (pin "3") (pinfunction "EN_3") (pintype "passive"))
      (node (ref "U2") (pin "4") (pinfunction "IN_4") (pintype "passive"))
      (node (ref "U4") (pin "24") (pinfunction "VU_24") (pintype "passive"))
    )
    (net (code "65") (name "A3V3") (class "Default")
      (node (ref "C13") (pin "1") (pinfunction "1_1") (pintype "passive"))
      (node (ref "C15") (pin "1") (pinfunction "1_1") (pintype "passive"))
      (node (ref "C23") (pin "2") (pinfunction "2_2") (pintype "passive"))
      (node (ref "C6") (pin "2") (pinfunction "2_2") (pintype "passive"))
      (node (ref "C7") (pin "2") (pinfunction "2_2") (pintype "passive"))
      (node (ref "FB1") (pin "2") (pinfunction "2_2") (pintype "passive"))
      (node (ref "FB3") (pin "1") (pintype "passive"))
      (node (ref "R22") (pin "1") (pinfunction "1_1") (pintype "passive"))
      (node (ref "R23") (pin "1") (pinfunction "1_1") (pintype "passive"))
      (node (ref "R34") (pin "1") (pinfunction "1_1") (pintype "passive"))
      (node (ref "TP7") (pin "1") (pinfunction "1_1") (pintype "passive"))
      (node (ref "U1") (pin "5") (pinfunction "VOUT_5") (pintype "passive"))
      (node (ref "U5") (pin "4") (pinfunction "VDDD_4") (pintype "passive"))
    )
    (net (code "66") (name "D3V3") (class "Default")
      (node (ref "C11") (pin "2") (pinfunction "2_2") (pintype "passive"))
      (node (ref "C12") (pin "2") (pinfunction "2_2") (pintype "passive"))
      (node (ref "C33") (pin "2") (pinfunction "2_2") (pintype "passive"))
      (node (ref "C34") (pin "2") (pinfunction "2_2") (pintype "passive"))
      (node (ref "C9") (pin "2") (pinfunction "2_2") (pintype "passive"))
      (node (ref "J1") (pin "4") (pinfunction "4_4") (pintype "passive"))
      (node (ref "J1") (pin "5") (pinfunction "5_5") (pintype "passive"))
      (node (ref "J2") (pin "4") (pinfunction "4_4") (pintype "passive"))
      (node (ref "J2") (pin "5") (pinfunction "5_5") (pintype "passive"))
      (node (ref "L1") (pin "2") (pinfunction "2_2") (pintype "passive"))
      (node (ref "R11") (pin "1") (pinfunction "1_1") (pintype "passive"))
      (node (ref "R2") (pin "2") (pinfunction "2_2") (pintype "passive"))
      (node (ref "R9") (pin "2") (pinfunction "2_2") (pintype "passive"))
      (node (ref "TP10") (pin "1") (pinfunction "1_1") (pintype "passive"))
      (node (ref "U6") (pin "3") (pinfunction "A2_3") (pintype "passive"))
      (node (ref "U6") (pin "8") (pinfunction "VCC_8") (pintype "passive"))
    )
    (net (code "67") (name "GND") (class "Default")
      (node (ref "C1") (pin "1") (pinfunction "1_1") (pintype "passive"))
      (node (ref "C10") (pin "1") (pinfunction "1_1") (pintype "passive"))
      (node (ref "C12") (pin "1") (pinfunction "1_1") (pintype "passive"))
      (node (ref "C13") (pin "2") (pinfunction "2_2") (pintype "passive"))
      (node (ref "C15") (pin "2") (pinfunction "2_2") (pintype "passive"))
      (node (ref "C2") (pin "1") (pinfunction "1_1") (pintype "passive"))
      (node (ref "C23") (pin "1") (pinfunction "1_1") (pintype "passive"))
      (node (ref "C3") (pin "1") (pinfunction "1_1") (pintype "passive"))
      (node (ref "C33") (pin "1") (pinfunction "1_1") (pintype "passive"))
      (node (ref "C34") (pin "1") (pinfunction "1_1") (pintype "passive"))
      (node (ref "C4") (pin "1") (pinfunction "1_1") (pintype "passive"))
      (node (ref "C5") (pin "1") (pinfunction "1_1") (pintype "passive"))
      (node (ref "C6") (pin "1") (pinfunction "1_1") (pintype "passive"))
      (node (ref "C7") (pin "1") (pinfunction "1_1") (pintype "passive"))
      (node (ref "C8") (pin "1") (pinfunction "1_1") (pintype "passive"))
      (node (ref "C9") (pin "1") (pinfunction "1_1") (pintype "passive"))
      (node (ref "CN1") (pin "4") (pinfunction "4_4") (pintype "passive"))
      (node (ref "FB2") (pin "2") (pinfunction "2_2") (pintype "passive"))
      (node (ref "FB4") (pin "1") (pintype "passive"))
      (node (ref "J1") (pin "0") (pinfunction "GND_0") (pintype "passive"))
      (node (ref "J1") (pin "10") (pinfunction "10_10") (pintype "passive"))
      (node (ref "J1") (pin "13") (pinfunction "13_13") (pintype "passive"))
      (node (ref "J1") (pin "14") (pinfunction "14_14") (pintype "passive"))
      (node (ref "J1") (pin "16") (pinfunction "16_16") (pintype "passive"))
      (node (ref "J1") (pin "21") (pinfunction "21_21") (pintype "passive"))
      (node (ref "J1") (pin "3") (pinfunction "3_3") (pintype "passive"))
      (node (ref "J1") (pin "6") (pinfunction "6_6") (pintype "passive"))
      (node (ref "J1") (pin "9") (pinfunction "9_9") (pintype "passive"))
      (node (ref "J2") (pin "0") (pinfunction "GND_0") (pintype "passive"))
      (node (ref "J2") (pin "3") (pinfunction "3_3") (pintype "passive"))
      (node (ref "J2") (pin "30") (pinfunction "30_30") (pintype "passive"))
      (node (ref "J2") (pin "6") (pinfunction "6_6") (pintype "passive"))
      (node (ref "JP1") (pin "3") (pinfunction "3_3") (pintype "passive"))
      (node (ref "R1") (pin "1") (pinfunction "1_1") (pintype "passive"))
      (node (ref "R12") (pin "2") (pinfunction "2_2") (pintype "passive"))
      (node (ref "R13") (pin "1") (pinfunction "1_1") (pintype "passive"))
      (node (ref "R14") (pin "1") (pinfunction "1_1") (pintype "passive"))
      (node (ref "R15") (pin "1") (pinfunction "1_1") (pintype "passive"))
      (node (ref "R16") (pin "1") (pinfunction "1_1") (pintype "passive"))
      (node (ref "R19") (pin "2") (pinfunction "2_2") (pintype "passive"))
      (node (ref "R27") (pin "2") (pinfunction "2_2") (pintype "passive"))
      (node (ref "R28") (pin "2") (pinfunction "2_2") (pintype "passive"))
      (node (ref "R29") (pin "2") (pinfunction "2_2") (pintype "passive"))
      (node (ref "R3") (pin "2") (pinfunction "2_2") (pintype "passive"))
      (node (ref "R35") (pin "1") (pinfunction "1_1") (pintype "passive"))
      (node (ref "R4") (pin "2") (pinfunction "2_2") (pintype "passive"))
      (node (ref "TP3") (pin "1") (pinfunction "1_1") (pintype "passive"))
      (node (ref "TP4") (pin "1") (pinfunction "1_1") (pintype "passive"))
      (node (ref "U1") (pin "2") (pinfunction "GND_2") (pintype "passive"))
      (node (ref "U2") (pin "2") (pinfunction "GND_2") (pintype "passive"))
      (node (ref "U3") (pin "4") (pinfunction "Emiter_4") (pintype "passive"))
      (node (ref "U4") (pin "25") (pinfunction "GND_25") (pintype "passive"))
      (node (ref "U5") (pin "5") (pinfunction "VSSD_5") (pintype "passive"))
      (node (ref "U6") (pin "1") (pinfunction "A0_1") (pintype "passive"))
      (node (ref "U6") (pin "2") (pinfunction "A1_2") (pintype "passive"))
      (node (ref "U6") (pin "4") (pinfunction "GND_4") (pintype "passive"))
      (node (ref "U6") (pin "7") (pinfunction "WP_7") (pintype "passive"))
      (node (ref "USB1") (pin "1") (pinfunction "SH1_1") (pintype "passive"))
      (node (ref "USB1") (pin "2") (pinfunction "SH2_2") (pintype "passive"))
      (node (ref "USB1") (pin "3") (pinfunction "SH3_3") (pintype "passive"))
      (node (ref "USB1") (pin "4") (pinfunction "SH4_4") (pintype "passive"))
      (node (ref "USB1") (pin "A1") (pinfunction "GND_A1") (pintype "passive"))
      (node (ref "USB1") (pin "A12") (pinfunction "GND_A12") (pintype "passive"))
      (node (ref "USB1") (pin "B1") (pinfunction "GND_B1") (pintype "passive"))
      (node (ref "USB1") (pin "B12") (pinfunction "GND_B12") (pintype "passive"))
    )
    (net (code "68") (name "IN_AGND") (class "Default")
      (node (ref "C24") (pin "1") (pinfunction "1_1") (pintype "passive"))
      (node (ref "C25") (pin "1") (pinfunction "1_1") (pintype "passive"))
      (node (ref "C27") (pin "1") (pinfunction "1_1") (pintype "passive"))
      (node (ref "C29") (pin "1") (pinfunction "1_1") (pintype "passive"))
      (node (ref "C30") (pin "1") (pinfunction "1_1") (pintype "passive"))
      (node (ref "C31") (pin "1") (pinfunction "1_1") (pintype "passive"))
      (node (ref "C32") (pin "1") (pinfunction "1_1") (pintype "passive"))
      (node (ref "CN4") (pin "4") (pinfunction "4_4") (pintype "passive"))
      (node (ref "FB4") (pin "2") (pinfunction "2_2") (pintype "passive"))
      (node (ref "R31") (pin "2") (pinfunction "2_2") (pintype "passive"))
      (node (ref "R33") (pin "2") (pinfunction "2_2") (pintype "passive"))
      (node (ref "U7") (pin "9") (pinfunction "GND_9") (pintype "passive"))
    )
    (net (code "69") (name "Net-(C17-Pad2)") (class "Default")
      (node (ref "C17") (pin "2") (pinfunction "2_2") (pintype "passive"))
      (node (ref "R17") (pin "2") (pinfunction "2_2") (pintype "passive"))
      (node (ref "R18") (pin "1") (pinfunction "1_1") (pintype "passive"))
    )
    (net (code "70") (name "Net-(C19-Pad2)") (class "Default")
      (node (ref "C19") (pin "2") (pinfunction "2_2") (pintype "passive"))
      (node (ref "R21") (pin "2") (pinfunction "2_2") (pintype "passive"))
      (node (ref "R26") (pin "1") (pinfunction "1_1") (pintype "passive"))
    )
    (net (code "71") (name "Net-(C26-Pad1)") (class "Default")
      (node (ref "C26") (pin "1") (pinfunction "1_1") (pintype "passive"))
      (node (ref "R30") (pin "2") (pinfunction "2_2") (pintype "passive"))
      (node (ref "R31") (pin "1") (pinfunction "1_1") (pintype "passive"))
    )
    (net (code "72") (name "Net-(C28-Pad1)") (class "Default")
      (node (ref "C28") (pin "1") (pinfunction "1_1") (pintype "passive"))
      (node (ref "R32") (pin "1") (pinfunction "1_1") (pintype "passive"))
      (node (ref "R33") (pin "1") (pinfunction "1_1") (pintype "passive"))
    )
    (net (code "73") (name "Net-(D1-K)") (class "Default")
      (node (ref "D1") (pin "2") (pinfunction "K_2") (pintype "passive"))
      (node (ref "R1") (pin "2") (pinfunction "2_2") (pintype "passive"))
    )
    (net (code "74") (name "Net-(D3-K)") (class "Default")
      (node (ref "D3") (pin "2") (pinfunction "K_2") (pintype "passive"))
      (node (ref "R8") (pin "2") (pinfunction "2_2") (pintype "passive"))
      (node (ref "U3") (pin "1") (pinfunction "Anaode_1") (pintype "passive"))
    )
    (net (code "75") (name "Net-(D4-K)") (class "Default")
      (node (ref "D4") (pin "2") (pinfunction "K_2") (pintype "passive"))
      (node (ref "R13") (pin "2") (pinfunction "2_2") (pintype "passive"))
    )
    (net (code "76") (name "Net-(D5-K)") (class "Default")
      (node (ref "D5") (pin "2") (pinfunction "K_2") (pintype "passive"))
      (node (ref "R14") (pin "2") (pinfunction "2_2") (pintype "passive"))
    )
    (net (code "77") (name "Net-(D6-K)") (class "Default")
      (node (ref "D6") (pin "2") (pinfunction "K_2") (pintype "passive"))
      (node (ref "R15") (pin "2") (pinfunction "2_2") (pintype "passive"))
    )
    (net (code "78") (name "Net-(D7-K)") (class "Default")
      (node (ref "D7") (pin "2") (pinfunction "K_2") (pintype "passive"))
      (node (ref "R16") (pin "2") (pinfunction "2_2") (pintype "passive"))
    )
    (net (code "79") (name "Net-(U1-BYPASS)") (class "Default")
      (node (ref "C8") (pin "2") (pinfunction "2_2") (pintype "passive"))
      (node (ref "U1") (pin "4") (pinfunction "BYPASS_4") (pintype "passive"))
    )
    (net (code "80") (name "Net-(U2-EN)") (class "Default")
      (node (ref "R10") (pin "2") (pinfunction "2_2") (pintype "passive"))
      (node (ref "U2") (pin "1") (pinfunction "EN_1") (pintype "passive"))
    )
    (net (code "81") (name "Net-(U2-FB)") (class "Default")
      (node (ref "C11") (pin "1") (pinfunction "1_1") (pintype "passive"))
      (node (ref "R11") (pin "2") (pinfunction "2_2") (pintype "passive"))
      (node (ref "R12") (pin "1") (pinfunction "1_1") (pintype "passive"))
      (node (ref "U2") (pin "5") (pinfunction "FB_5") (pintype "passive"))
    )
    (net (code "82") (name "Net-(U2-Out)") (class "Default")
      (node (ref "L1") (pin "1") (pintype "passive"))
      (node (ref "U2") (pin "3") (pinfunction "Out_3") (pintype "passive"))
    )
    (net (code "83") (name "Net-(U5-BCK)") (class "Default")
      (node (ref "R20") (pin "2") (pinfunction "2_2") (pintype "passive"))
      (node (ref "U5") (pin "1") (pinfunction "BCK_1") (pintype "passive"))
    )
    (net (code "84") (name "Net-(U5-DATA1)") (class "Default")
      (node (ref "R25") (pin "2") (pinfunction "2_2") (pintype "passive"))
      (node (ref "U5") (pin "3") (pinfunction "DATA1_3") (pintype "passive"))
    )
    (net (code "85") (name "Net-(U5-DEEM{slash}CLKOUT)") (class "Default")
      (node (ref "R28") (pin "1") (pinfunction "1_1") (pintype "passive"))
      (node (ref "TP20") (pin "1") (pinfunction "1_1") (pintype "passive"))
      (node (ref "U5") (pin "9") (pinfunction "DEEM/CLKOUT_9") (pintype "passive"))
    )
    (net (code "86") (name "Net-(U5-PLL0)") (class "Default")
      (node (ref "R29") (pin "1") (pinfunction "1_1") (pintype "passive"))
      (node (ref "TP21") (pin "1") (pinfunction "1_1") (pintype "passive"))
      (node (ref "U5") (pin "10") (pinfunction "PLL0_10") (pintype "passive"))
    )
    (net (code "87") (name "Net-(U5-SYSCLK{slash}PLL1)") (class "Default")
      (node (ref "R19") (pin "1") (pinfunction "1_1") (pintype "passive"))
      (node (ref "TP14") (pin "1") (pinfunction "1_1") (pintype "passive"))
      (node (ref "U5") (pin "6") (pinfunction "SYSCLK/PLL1_6") (pintype "passive"))
    )
    (net (code "88") (name "Net-(U5-VDDA)") (class "Default")
      (node (ref "C14") (pin "1") (pinfunction "1_1") (pintype "passive"))
      (node (ref "C16") (pin "1") (pinfunction "1_1") (pintype "passive"))
      (node (ref "FB1") (pin "1") (pintype "passive"))
      (node (ref "U5") (pin "13") (pinfunction "VDDA_13") (pintype "passive"))
    )
    (net (code "89") (name "Net-(U5-VOUTL)") (class "Default")
      (node (ref "C17") (pin "1") (pinfunction "1_1") (pintype "passive"))
      (node (ref "U5") (pin "14") (pinfunction "VOUTL_14") (pintype "passive"))
    )
    (net (code "90") (name "Net-(U5-VOUTR)") (class "Default")
      (node (ref "C19") (pin "1") (pinfunction "1_1") (pintype "passive"))
      (node (ref "U5") (pin "16") (pinfunction "VOUTR_16") (pintype "passive"))
    )
    (net (code "91") (name "Net-(U5-VREF(DAC))") (class "Default")
      (node (ref "C21") (pin "2") (pinfunction "2_2") (pintype "passive"))
      (node (ref "C22") (pin "2") (pinfunction "2_2") (pintype "passive"))
      (node (ref "U5") (pin "12") (pinfunction "VREF(DAC)_12") (pintype "passive"))
    )
    (net (code "92") (name "Net-(U5-WS)") (class "Default")
      (node (ref "R24") (pin "2") (pinfunction "2_2") (pintype "passive"))
      (node (ref "U5") (pin "2") (pinfunction "WS_2") (pintype "passive"))
    )
    (net (code "93") (name "Net-(U7-AINL)") (class "Default")
      (node (ref "C28") (pin "2") (pinfunction "2_2") (pintype "passive"))
      (node (ref "C31") (pin "2") (pinfunction "2_2") (pintype "passive"))
      (node (ref "U7") (pin "6") (pinfunction "AINL_6") (pintype "passive"))
    )
    (net (code "94") (name "Net-(U7-AINR)") (class "Default")
      (node (ref "C26") (pin "2") (pinfunction "2_2") (pintype "passive"))
      (node (ref "C27") (pin "2") (pinfunction "2_2") (pintype "passive"))
      (node (ref "U7") (pin "8") (pinfunction "AINR_8") (pintype "passive"))
    )
    (net (code "95") (name "Net-(U7-FLR+)") (class "Default")
      (node (ref "C32") (pin "2") (pinfunction "2_2") (pintype "passive"))
      (node (ref "U7") (pin "5") (pinfunction "FLR+_5") (pintype "passive"))
    )
    (net (code "96") (name "Net-(U7-VA)") (class "Default")
      (node (ref "C24") (pin "2") (pinfunction "2_2") (pintype "passive"))
      (node (ref "C25") (pin "2") (pinfunction "2_2") (pintype "passive"))
      (node (ref "FB3") (pin "2") (pinfunction "2_2") (pintype "passive"))
      (node (ref "U7") (pin "10") (pinfunction "VA_10") (pintype "passive"))
    )
    (net (code "97") (name "Net-(U7-VQ)") (class "Default")
      (node (ref "C29") (pin "2") (pinfunction "2_2") (pintype "passive"))
      (node (ref "C30") (pin "2") (pinfunction "2_2") (pintype "passive"))
      (node (ref "U7") (pin "7") (pinfunction "VQ_7") (pintype "passive"))
    )
    (net (code "98") (name "Net-(USB1-CC1)") (class "Default")
      (node (ref "R3") (pin "1") (pinfunction "1_1") (pintype "passive"))
      (node (ref "USB1") (pin "A5") (pinfunction "CC1_A5") (pintype "passive"))
    )
    (net (code "99") (name "Net-(USB1-CC2)") (class "Default")
      (node (ref "R4") (pin "1") (pinfunction "1_1") (pintype "passive"))
      (node (ref "USB1") (pin "B5") (pinfunction "CC2_B5") (pintype "passive"))
    )
    (net (code "100") (name "OUT_AGND") (class "Default")
      (node (ref "C14") (pin "2") (pinfunction "2_2") (pintype "passive"))
      (node (ref "C16") (pin "2") (pinfunction "2_2") (pintype "passive"))
      (node (ref "C18") (pin "1") (pinfunction "1_1") (pintype "passive"))
      (node (ref "C20") (pin "1") (pinfunction "1_1") (pintype "passive"))
      (node (ref "C21") (pin "1") (pinfunction "1_1") (pintype "passive"))
      (node (ref "C22") (pin "1") (pinfunction "1_1") (pintype "passive"))
      (node (ref "CN3") (pin "4") (pinfunction "4_4") (pintype "passive"))
      (node (ref "FB2") (pin "1") (pintype "passive"))
      (node (ref "R18") (pin "2") (pinfunction "2_2") (pintype "passive"))
      (node (ref "R26") (pin "2") (pinfunction "2_2") (pintype "passive"))
      (node (ref "U5") (pin "15") (pinfunction "VSSA_15") (pintype "passive"))
    )
    (net (code "101") (name "VBUS") (class "Default")
      (node (ref "D2") (pin "1") (pinfunction "A_1") (pintype "passive"))
      (node (ref "USB1") (pin "A4") (pinfunction "VBUS_A4") (pintype "passive"))
      (node (ref "USB1") (pin "A9") (pinfunction "VBUS_A9") (pintype "passive"))
      (node (ref "USB1") (pin "B4") (pinfunction "VBUS_B4") (pintype "passive"))
      (node (ref "USB1") (pin "B9") (pinfunction "VBUS_B9") (pintype "passive"))
    )
    (net (code "102") (name "unconnected-(J1-Pad26)") (class "Default")
      (node (ref "J1") (pin "26") (pinfunction "26_26") (pintype "passive+no_connect"))
    )
    (net (code "103") (name "unconnected-(J1-Pad27)") (class "Default")
      (node (ref "J1") (pin "27") (pinfunction "27_27") (pintype "passive+no_connect"))
    )
    (net (code "104") (name "unconnected-(J1-Pad28)") (class "Default")
      (node (ref "J1") (pin "28") (pinfunction "28_28") (pintype "passive+no_connect"))
    )
    (net (code "105") (name "unconnected-(J1-Pad29)") (class "Default")
      (node (ref "J1") (pin "29") (pinfunction "29_29") (pintype "passive+no_connect"))
    )
    (net (code "106") (name "unconnected-(J1-Pad30)") (class "Default")
      (node (ref "J1") (pin "30") (pinfunction "30_30") (pintype "passive+no_connect"))
    )
    (net (code "107") (name "unconnected-(SP1-Pad1)") (class "Default")
      (node (ref "SP1") (pin "1") (pinfunction "1_1") (pintype "passive"))
    )
    (net (code "108") (name "unconnected-(SP2-Pad1)") (class "Default")
      (node (ref "SP2") (pin "1") (pinfunction "1_1") (pintype "passive"))
    )
    (net (code "109") (name "unconnected-(SP3-Pad1)") (class "Default")
      (node (ref "SP3") (pin "1") (pinfunction "1_1") (pintype "passive"))
    )
    (net (code "110") (name "unconnected-(SP4-Pad1)") (class "Default")
      (node (ref "SP4") (pin "1") (pinfunction "1_1") (pintype "passive"))
    )
    (net (code "111") (name "unconnected-(U3-Base-Pad6)") (class "Default")
      (node (ref "U3") (pin "6") (pinfunction "Base_6") (pintype "passive"))
    )
    (net (code "112") (name "unconnected-(USB1-RX1+-PadB11)") (class "Default")
      (node (ref "USB1") (pin "B11") (pinfunction "RX1+_B11") (pintype "passive"))
    )
    (net (code "113") (name "unconnected-(USB1-RX1--PadB10)") (class "Default")
      (node (ref "USB1") (pin "B10") (pinfunction "RX1-_B10") (pintype "passive"))
    )
    (net (code "114") (name "unconnected-(USB1-RX2+-PadA11)") (class "Default")
      (node (ref "USB1") (pin "A11") (pinfunction "RX2+_A11") (pintype "passive"))
    )
    (net (code "115") (name "unconnected-(USB1-RX2--PadA10)") (class "Default")
      (node (ref "USB1") (pin "A10") (pinfunction "RX2-_A10") (pintype "passive"))
    )
    (net (code "116") (name "unconnected-(USB1-SBU1-PadA8)") (class "Default")
      (node (ref "USB1") (pin "A8") (pinfunction "SBU1_A8") (pintype "passive"))
    )
    (net (code "117") (name "unconnected-(USB1-SBU2-PadB8)") (class "Default")
      (node (ref "USB1") (pin "B8") (pinfunction "SBU2_B8") (pintype "passive"))
    )
    (net (code "118") (name "unconnected-(USB1-TX1+-PadA2)") (class "Default")
      (node (ref "USB1") (pin "A2") (pinfunction "TX1+_A2") (pintype "passive"))
    )
    (net (code "119") (name "unconnected-(USB1-TX1--PadA3)") (class "Default")
      (node (ref "USB1") (pin "A3") (pinfunction "TX1-_A3") (pintype "passive"))
    )
    (net (code "120") (name "unconnected-(USB1-TX2+-PadB2)") (class "Default")
      (node (ref "USB1") (pin "B2") (pinfunction "TX2+_B2") (pintype "passive"))
    )
    (net (code "121") (name "unconnected-(USB1-TX2--PadB3)") (class "Default")
      (node (ref "USB1") (pin "B3") (pinfunction "TX2-_B3") (pintype "passive"))
    )
  )
)
